# SparkFun_Thing_Plus_RP2350.net
KiCad netlist of a schematic drawn in EAGLE
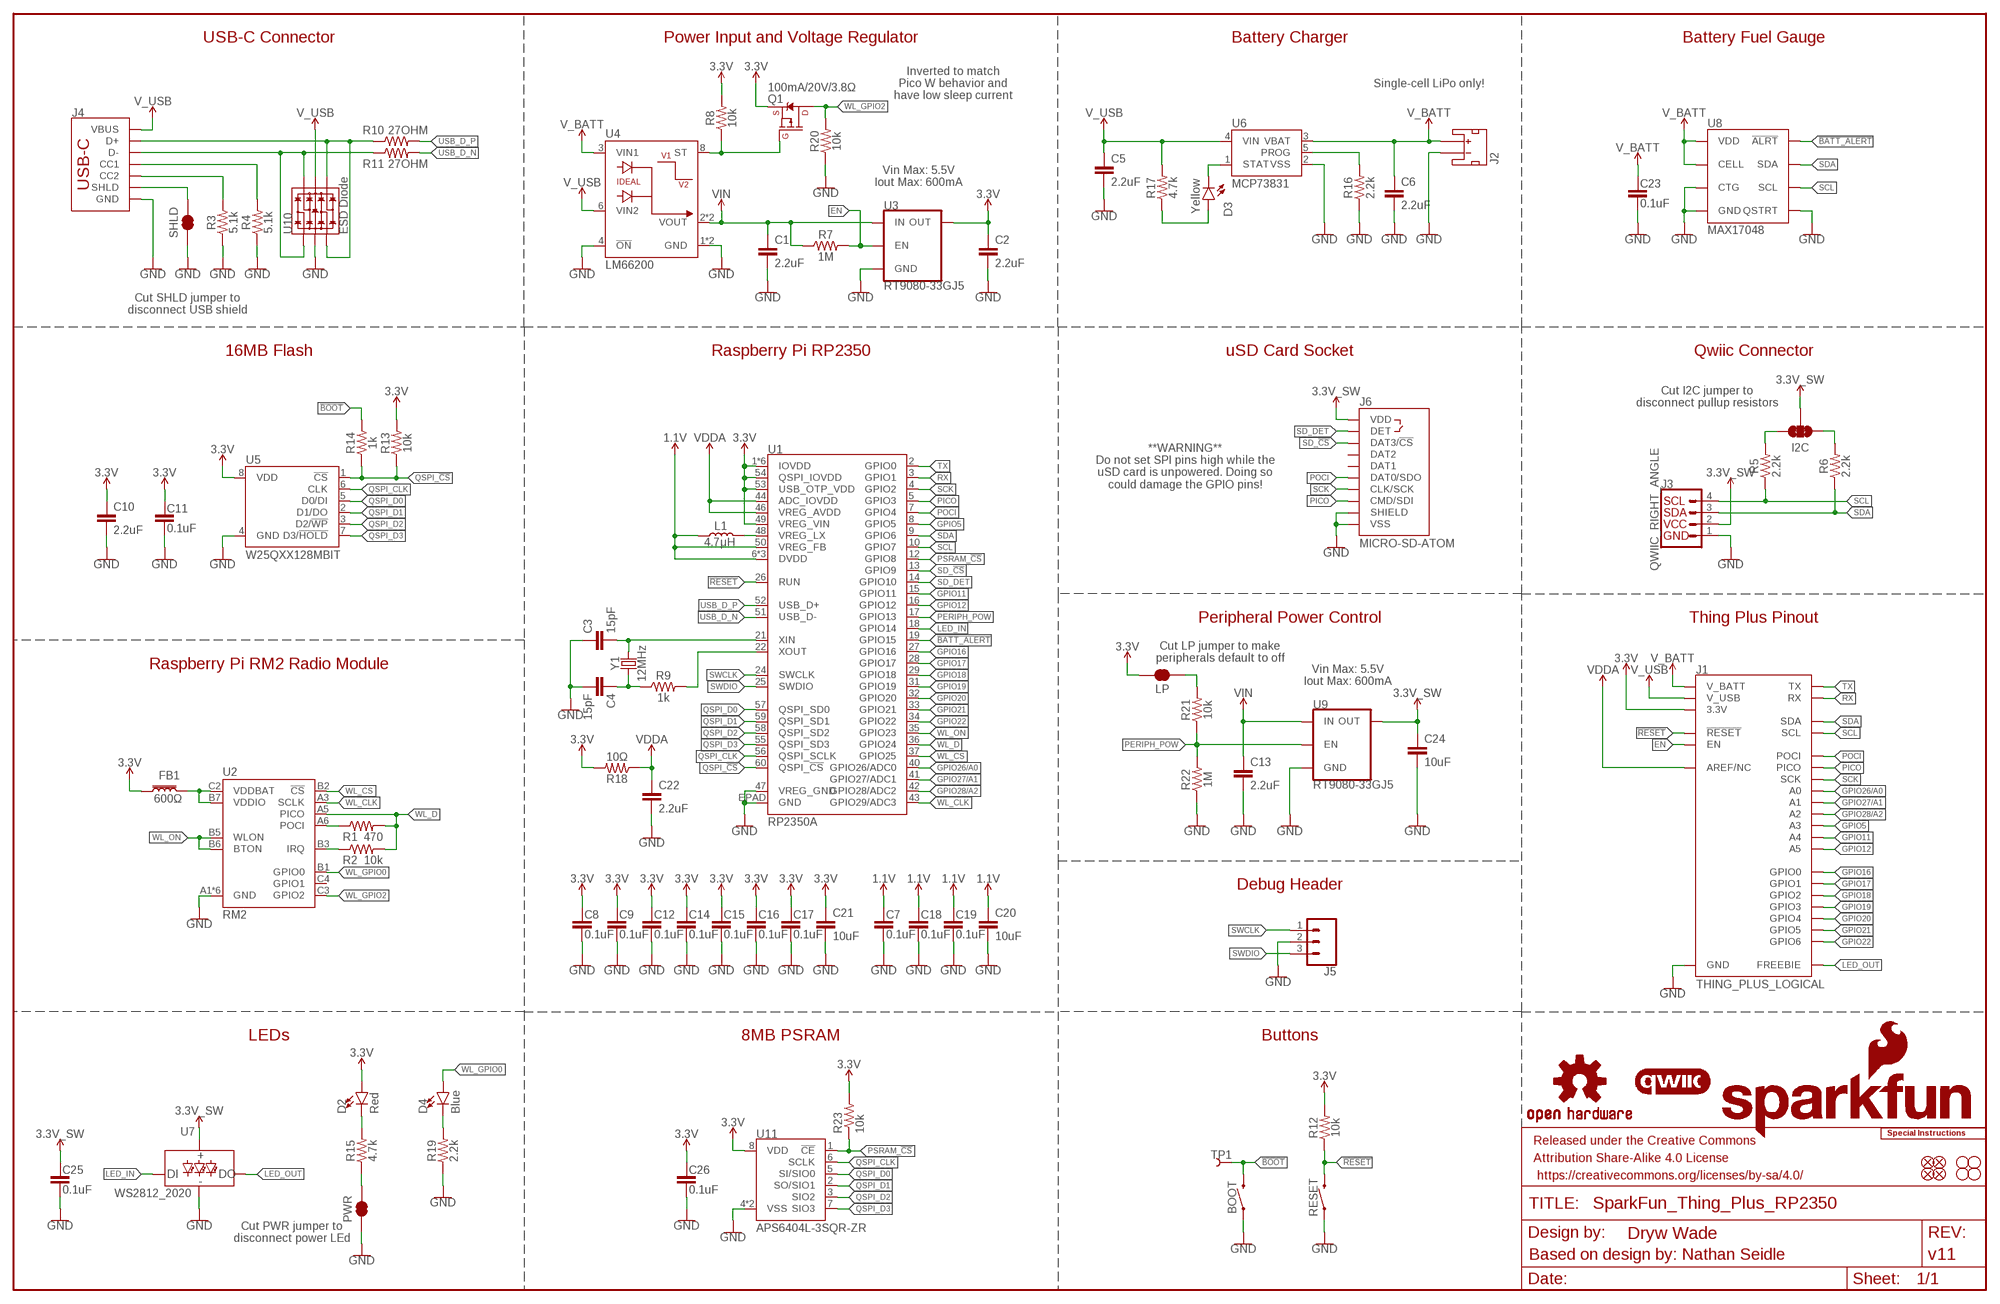
[diagram p0: schematic, sheet 1]

(export (version "E")
  (design (tool "Eeschema 10.0.6"))
  (components
    (comp (ref "BOOT")
      (value "MOMENTARY-SWITCH-SPST-SMD-4.6X2.8MM")
      (footprint "eagle-import:TACTILE_SWITCH_SMD_4.6X2.8MM")
      (libsource (lib "eagle-import") (part "MOMENTARY-SWITCH-SPST-SMD-4.6X2.8MM"))
    )
    (comp (ref "C1")
      (value "2.2uF")
      (footprint "eagle-import:0402-TIGHT")
      (libsource (lib "eagle-import") (part "2.2UF-0402_TIGHT-10V-10%-X5R"))
    )
    (comp (ref "C2")
      (value "2.2uF")
      (footprint "eagle-import:0402-TIGHT")
      (libsource (lib "eagle-import") (part "2.2UF-0402_TIGHT-10V-10%-X5R"))
    )
    (comp (ref "C3")
      (value "15pF")
      (footprint "eagle-import:0402-TIGHT")
      (libsource (lib "eagle-import") (part "15PF-0402T-50V-5%"))
    )
    (comp (ref "C4")
      (value "15pF")
      (footprint "eagle-import:0402-TIGHT")
      (libsource (lib "eagle-import") (part "15PF-0402T-50V-5%"))
    )
    (comp (ref "C5")
      (value "2.2uF")
      (footprint "eagle-import:0402-TIGHT")
      (libsource (lib "eagle-import") (part "2.2UF-0402_TIGHT-10V-10%-X5R"))
    )
    (comp (ref "C6")
      (value "2.2uF")
      (footprint "eagle-import:0402-TIGHT")
      (libsource (lib "eagle-import") (part "2.2UF-0402_TIGHT-10V-10%-X5R"))
    )
    (comp (ref "C7")
      (value "0.1uF")
      (footprint "eagle-import:0402-TIGHT")
      (libsource (lib "eagle-import") (part "0.1UF-0402T-6.3V-10%-X7R"))
    )
    (comp (ref "C8")
      (value "0.1uF")
      (footprint "eagle-import:0402-TIGHT")
      (libsource (lib "eagle-import") (part "0.1UF-0402T-6.3V-10%-X7R"))
    )
    (comp (ref "C9")
      (value "0.1uF")
      (footprint "eagle-import:0402-TIGHT")
      (libsource (lib "eagle-import") (part "0.1UF-0402T-6.3V-10%-X7R"))
    )
    (comp (ref "C10")
      (value "2.2uF")
      (footprint "eagle-import:0402-TIGHT")
      (libsource (lib "eagle-import") (part "2.2UF-0402_TIGHT-10V-10%-X5R"))
    )
    (comp (ref "C11")
      (value "0.1uF")
      (footprint "eagle-import:0402-TIGHT")
      (libsource (lib "eagle-import") (part "0.1UF-0402T-6.3V-10%-X7R"))
    )
    (comp (ref "C12")
      (value "0.1uF")
      (footprint "eagle-import:0402-TIGHT")
      (libsource (lib "eagle-import") (part "0.1UF-0402T-6.3V-10%-X7R"))
    )
    (comp (ref "C13")
      (value "2.2uF")
      (footprint "eagle-import:0402-TIGHT")
      (libsource (lib "eagle-import") (part "2.2UF-0402_TIGHT-10V-10%-X5R"))
    )
    (comp (ref "C14")
      (value "0.1uF")
      (footprint "eagle-import:0402-TIGHT")
      (libsource (lib "eagle-import") (part "0.1UF-0402T-6.3V-10%-X7R"))
    )
    (comp (ref "C15")
      (value "0.1uF")
      (footprint "eagle-import:0402-TIGHT")
      (libsource (lib "eagle-import") (part "0.1UF-0402T-6.3V-10%-X7R"))
    )
    (comp (ref "C16")
      (value "0.1uF")
      (footprint "eagle-import:0402-TIGHT")
      (libsource (lib "eagle-import") (part "0.1UF-0402T-6.3V-10%-X7R"))
    )
    (comp (ref "C17")
      (value "0.1uF")
      (footprint "eagle-import:0402-TIGHT")
      (libsource (lib "eagle-import") (part "0.1UF-0402T-6.3V-10%-X7R"))
    )
    (comp (ref "C18")
      (value "0.1uF")
      (footprint "eagle-import:0402-TIGHT")
      (libsource (lib "eagle-import") (part "0.1UF-0402T-6.3V-10%-X7R"))
    )
    (comp (ref "C19")
      (value "0.1uF")
      (footprint "eagle-import:0402-TIGHT")
      (libsource (lib "eagle-import") (part "0.1UF-0402T-6.3V-10%-X7R"))
    )
    (comp (ref "C20")
      (value "10uF")
      (footprint "eagle-import:0402-TIGHT")
      (libsource (lib "eagle-import") (part "10UF-0402T-6.3V-20%"))
    )
    (comp (ref "C21")
      (value "10uF")
      (footprint "eagle-import:0402-TIGHT")
      (libsource (lib "eagle-import") (part "10UF-0402T-6.3V-20%"))
    )
    (comp (ref "C22")
      (value "2.2uF")
      (footprint "eagle-import:0402-TIGHT")
      (libsource (lib "eagle-import") (part "2.2UF-0402_TIGHT-10V-10%-X5R"))
    )
    (comp (ref "C23")
      (value "0.1uF")
      (footprint "eagle-import:0402-TIGHT")
      (libsource (lib "eagle-import") (part "0.1UF-0402T-6.3V-10%-X7R"))
    )
    (comp (ref "C24")
      (value "10uF")
      (footprint "eagle-import:0402-TIGHT")
      (libsource (lib "eagle-import") (part "10UF-0402T-6.3V-20%"))
    )
    (comp (ref "C25")
      (value "0.1uF")
      (footprint "eagle-import:0402-TIGHT")
      (libsource (lib "eagle-import") (part "0.1UF-0402T-6.3V-10%-X7R"))
    )
    (comp (ref "C26")
      (value "0.1uF")
      (footprint "eagle-import:0402-TIGHT")
      (libsource (lib "eagle-import") (part "0.1UF-0402T-6.3V-10%-X7R"))
    )
    (comp (ref "D2")
      (value "Red")
      (footprint "eagle-import:LED-0603")
      (libsource (lib "eagle-import") (part "LED-RED_0603-KB"))
    )
    (comp (ref "D3")
      (value "Yellow")
      (footprint "eagle-import:LED-0603")
      (libsource (lib "eagle-import") (part "LED-YELLOW0603"))
    )
    (comp (ref "D4")
      (value "Blue")
      (footprint "eagle-import:LED-0603")
      (libsource (lib "eagle-import") (part "LED-BLUE0603"))
    )
    (comp (ref "FB1")
      (value "600Ω")
      (footprint "eagle-import:0805")
      (libsource (lib "eagle-import") (part "FERRITE_BEAD-0805-600Ω-100MHZ"))
    )
    (comp (ref "FD1")
      (value "FIDUCIALUFIDUCIAL")
      (footprint "eagle-import:FIDUCIAL-MICRO")
      (libsource (lib "eagle-import") (part "FIDUCIALUFIDUCIAL"))
    )
    (comp (ref "FD2")
      (value "FIDUCIALUFIDUCIAL")
      (footprint "eagle-import:FIDUCIAL-MICRO")
      (libsource (lib "eagle-import") (part "FIDUCIALUFIDUCIAL"))
    )
    (comp (ref "FD3")
      (value "FIDUCIALUFIDUCIAL")
      (footprint "eagle-import:FIDUCIAL-MICRO")
      (libsource (lib "eagle-import") (part "FIDUCIALUFIDUCIAL"))
    )
    (comp (ref "FD4")
      (value "FIDUCIALUFIDUCIAL")
      (footprint "eagle-import:FIDUCIAL-MICRO")
      (libsource (lib "eagle-import") (part "FIDUCIALUFIDUCIAL"))
    )
    (comp (ref "FRAME1")
      (value "FRAME-LEDGER")
      (footprint "eagle-import:CREATIVE_COMMONS")
      (fields (field (name "DESIGNER") "Dryw Wade") (field (name "REV") "v11"))
      (libsource (lib "eagle-import") (part "FRAME-LEDGER"))
    )
    (comp (ref "H1")
      (value "STAND-OFF")
      (footprint "eagle-import:STAND-OFF")
      (libsource (lib "eagle-import") (part "STAND-OFF"))
    )
    (comp (ref "H2")
      (value "STAND-OFF")
      (footprint "eagle-import:STAND-OFF")
      (libsource (lib "eagle-import") (part "STAND-OFF"))
    )
    (comp (ref "H3")
      (value "STAND-OFF")
      (footprint "eagle-import:STAND-OFF")
      (libsource (lib "eagle-import") (part "STAND-OFF"))
    )
    (comp (ref "H4")
      (value "STAND-OFF")
      (footprint "eagle-import:STAND-OFF")
      (libsource (lib "eagle-import") (part "STAND-OFF"))
    )
    (comp (ref "I2C")
      (value "JUMPER-SMT_3_2-NC_TRACE_SILK")
      (footprint "eagle-import:SMT-JUMPER_3_2-NC_TRACE_SILK")
      (libsource (lib "eagle-import") (part "JUMPER-SMT_3_2-NC_TRACE_SILK"))
    )
    (comp (ref "J1")
      (value "THING_PLUS_LOGICAL")
      (footprint "eagle-import:THING_PLUS")
      (libsource (lib "eagle-import") (part "THING_PLUS_LOGICAL"))
    )
    (comp (ref "J2")
      (value "JST_2MM_MALE")
      (footprint "eagle-import:JST-2-SMD")
      (libsource (lib "eagle-import") (part "JST_2MM_MALE"))
    )
    (comp (ref "J3")
      (value "QWIIC_RIGHT_ANGLE")
      (footprint "eagle-import:JST04_1MM_RA")
      (libsource (lib "eagle-import") (part "QWIIC_CONNECTORJS-1MM"))
    )
    (comp (ref "J4")
      (value "USB_C_4-LAYER_PADS")
      (footprint "eagle-import:USB-C-16P_4LAYER-PADS")
      (libsource (lib "eagle-import") (part "USB_C_4-LAYER_PADS"))
    )
    (comp (ref "J5")
      (value "CONN_031X03_NO_SILK")
      (footprint "eagle-import:1X03_NO_SILK")
      (libsource (lib "eagle-import") (part "CONN_031X03_NO_SILK"))
    )
    (comp (ref "J6")
      (value "MICRO-SD-ATOM")
      (footprint "eagle-import:MICROSD_ATOM")
      (libsource (lib "eagle-import") (part "MICRO-SD-ATOM"))
    )
    (comp (ref "L1")
      (value "4.7μH")
      (footprint "eagle-import:1008(2520)")
      (libsource (lib "eagle-import") (part "4.7μH_SHIELDED_INDUCTOR"))
    )
    (comp (ref "LOGO1")
      (value "SFE_LOGO_NAME_FLAME.1_INCH")
      (footprint "eagle-import:SFE_LOGO_NAME_FLAME_.1")
      (libsource (lib "eagle-import") (part "SFE_LOGO_NAME_FLAME.1_INCH"))
    )
    (comp (ref "LOGO2")
      (value "OSHW-LOGOS")
      (footprint "eagle-import:OSHW-LOGO-S")
      (libsource (lib "eagle-import") (part "OSHW-LOGOS"))
    )
    (comp (ref "LOGO3")
      (value "QWIIC_LOGO_4MM")
      (footprint "eagle-import:QWIIC_4MM")
      (libsource (lib "eagle-import") (part "QWIIC_LOGO_4MM"))
    )
    (comp (ref "LOGO5")
      (value "SPECIAL_INSTRUCTIONS-ORDERING")
      (footprint "eagle-import:ORDERING_INSTRUCTIONS")
      (libsource (lib "eagle-import") (part "SPECIAL_INSTRUCTIONS-ORDERING"))
    )
    (comp (ref "LP")
      (value "JUMPER-SMT_2_NC_TRACE_SILK")
      (footprint "eagle-import:SMT-JUMPER_2_NC_TRACE_SILK")
      (libsource (lib "eagle-import") (part "JUMPER-SMT_2_NC_TRACE_SILK"))
    )
    (comp (ref "PWR")
      (value "JUMPER-SMT_2_NC_TRACE_SILK")
      (footprint "eagle-import:SMT-JUMPER_2_NC_TRACE_SILK")
      (libsource (lib "eagle-import") (part "JUMPER-SMT_2_NC_TRACE_SILK"))
    )
    (comp (ref "Q1")
      (value "100mA/20V/3.8Ω")
      (footprint "eagle-import:SOT-416FL")
      (libsource (lib "eagle-import") (part "MOSFET_PCH-RE1C001ZPTL"))
    )
    (comp (ref "R1")
      (value "470")
      (footprint "eagle-import:0402-TIGHT")
      (libsource (lib "eagle-import") (part "470OHM-0402-TIGHT-1/16W-1%"))
    )
    (comp (ref "R2")
      (value "10k")
      (footprint "eagle-import:0402-TIGHT")
      (libsource (lib "eagle-import") (part "10KOHM-0402T-1/16W-1%"))
    )
    (comp (ref "R3")
      (value "5.1k")
      (footprint "eagle-import:0402-TIGHT")
      (libsource (lib "eagle-import") (part "5.1KOHM-0402T-1/16W-1%"))
    )
    (comp (ref "R4")
      (value "5.1k")
      (footprint "eagle-import:0402-TIGHT")
      (libsource (lib "eagle-import") (part "5.1KOHM-0402T-1/16W-1%"))
    )
    (comp (ref "R5")
      (value "2.2k")
      (footprint "eagle-import:0402-TIGHT")
      (libsource (lib "eagle-import") (part "2.2KOHM-0402T-1/16W-1%"))
    )
    (comp (ref "R6")
      (value "2.2k")
      (footprint "eagle-import:0402-TIGHT")
      (libsource (lib "eagle-import") (part "2.2KOHM-0402T-1/16W-1%"))
    )
    (comp (ref "R7")
      (value "1M")
      (footprint "eagle-import:0402-TIGHT")
      (libsource (lib "eagle-import") (part "1MOHM-0402T-1/16W-5%"))
    )
    (comp (ref "R8")
      (value "10k")
      (footprint "eagle-import:0402-TIGHT")
      (libsource (lib "eagle-import") (part "10KOHM-0402T-1/16W-1%"))
    )
    (comp (ref "R9")
      (value "1k")
      (footprint "eagle-import:0402-TIGHT")
      (libsource (lib "eagle-import") (part "1KOHM-0402T-1/16W-1%"))
    )
    (comp (ref "R10")
      (value "27OHM")
      (footprint "eagle-import:0402-TIGHT")
      (libsource (lib "eagle-import") (part "27OHM"))
    )
    (comp (ref "R11")
      (value "27OHM")
      (footprint "eagle-import:0402-TIGHT")
      (libsource (lib "eagle-import") (part "27OHM"))
    )
    (comp (ref "R12")
      (value "10k")
      (footprint "eagle-import:0402-TIGHT")
      (libsource (lib "eagle-import") (part "10KOHM-0402T-1/16W-1%"))
    )
    (comp (ref "R13")
      (value "10k")
      (footprint "eagle-import:0402-TIGHT")
      (libsource (lib "eagle-import") (part "10KOHM-0402T-1/16W-1%"))
    )
    (comp (ref "R14")
      (value "1k")
      (footprint "eagle-import:0402-TIGHT")
      (libsource (lib "eagle-import") (part "1KOHM-0402T-1/16W-1%"))
    )
    (comp (ref "R15")
      (value "4.7k")
      (footprint "eagle-import:0402-TIGHT")
      (libsource (lib "eagle-import") (part "4.7KOHM-0402T-1/16W-1%"))
    )
    (comp (ref "R16")
      (value "2.2k")
      (footprint "eagle-import:0402-TIGHT")
      (libsource (lib "eagle-import") (part "2.2KOHM-0402T-1/16W-1%"))
    )
    (comp (ref "R17")
      (value "4.7k")
      (footprint "eagle-import:0402-TIGHT")
      (libsource (lib "eagle-import") (part "4.7KOHM-0402T-1/16W-1%"))
    )
    (comp (ref "R18")
      (value "10Ω")
      (footprint "eagle-import:0402-TIGHT")
      (libsource (lib "eagle-import") (part "10OHM-0402-1/16W-5%"))
    )
    (comp (ref "R19")
      (value "2.2k")
      (footprint "eagle-import:0402-TIGHT")
      (libsource (lib "eagle-import") (part "2.2KOHM-0402T-1/16W-1%"))
    )
    (comp (ref "R20")
      (value "10k")
      (footprint "eagle-import:0402-TIGHT")
      (libsource (lib "eagle-import") (part "10KOHM-0402T-1/16W-1%"))
    )
    (comp (ref "R21")
      (value "10k")
      (footprint "eagle-import:0402-TIGHT")
      (libsource (lib "eagle-import") (part "10KOHM-0402T-1/16W-1%"))
    )
    (comp (ref "R22")
      (value "1M")
      (footprint "eagle-import:0402-TIGHT")
      (libsource (lib "eagle-import") (part "1MOHM-0402T-1/16W-5%"))
    )
    (comp (ref "R23")
      (value "10k")
      (footprint "eagle-import:0402-TIGHT")
      (libsource (lib "eagle-import") (part "10KOHM-0402T-1/16W-1%"))
    )
    (comp (ref "RESET")
      (value "MOMENTARY-SWITCH-SPST-SMD-4.6X2.8MM")
      (footprint "eagle-import:TACTILE_SWITCH_SMD_4.6X2.8MM")
      (libsource (lib "eagle-import") (part "MOMENTARY-SWITCH-SPST-SMD-4.6X2.8MM"))
    )
    (comp (ref "SHLD")
      (value "JUMPER-SMT_2_NC_TRACE_SILK")
      (footprint "eagle-import:SMT-JUMPER_2_NC_TRACE_SILK")
      (libsource (lib "eagle-import") (part "JUMPER-SMT_2_NC_TRACE_SILK"))
    )
    (comp (ref "TP1")
      (value "TEST-POINT3X5")
      (footprint "eagle-import:PAD.03X.05")
      (libsource (lib "eagle-import") (part "TEST-POINT3X5"))
    )
    (comp (ref "U1")
      (value "RP2350A")
      (footprint "eagle-import:RP2350A")
      (libsource (lib "eagle-import") (part "RP2350A"))
    )
    (comp (ref "U2")
      (value "RM2")
      (footprint "eagle-import:RM2")
      (libsource (lib "eagle-import") (part "RM2"))
    )
    (comp (ref "U3")
      (value "RT9080-33GJ5")
      (footprint "eagle-import:SOT23-5")
      (libsource (lib "eagle-import") (part "V_REG_RT9080-33GJ5"))
    )
    (comp (ref "U4")
      (value "LM66200")
      (footprint "eagle-import:SOT8")
      (libsource (lib "eagle-import") (part "IDEAL_DIODE_DUAL_LM66200"))
    )
    (comp (ref "U5")
      (value "W25QXX128MBIT")
      (footprint "eagle-import:WSON-8-6X5-SKINNY_CENTERPAD")
      (libsource (lib "eagle-import") (part "W25QXX128MBIT-6X5-SKINNY_CENTER"))
    )
    (comp (ref "U6")
      (value "MCP73831")
      (footprint "eagle-import:SOT23-5")
      (libsource (lib "eagle-import") (part "MCP73831"))
    )
    (comp (ref "U7")
      (value "WS2812_2020")
      (footprint "eagle-import:WS2812-2020")
      (libsource (lib "eagle-import") (part "WS2812_2020"))
    )
    (comp (ref "U8")
      (value "MAX17048")
      (footprint "eagle-import:DFN-8")
      (libsource (lib "eagle-import") (part "MAX17048DFN8"))
    )
    (comp (ref "U9")
      (value "RT9080-33GJ5")
      (footprint "eagle-import:SOT23-5")
      (libsource (lib "eagle-import") (part "V_REG_RT9080-33GJ5"))
    )
    (comp (ref "U10")
      (value "ESD Diode")
      (footprint "eagle-import:SOT-23-6")
      (libsource (lib "eagle-import") (part "TVS_DIODE_ARRAY_DT1042-04SO-7"))
    )
    (comp (ref "U11")
      (value "APS6404L-3SQR-ZR")
      (footprint "eagle-import:APS6404L-3SQR-ZR")
      (libsource (lib "eagle-import") (part "APS6404L-3SQR-ZR"))
    )
    (comp (ref "Y1")
      (value "12MHz")
      (footprint "eagle-import:CRYSTAL-SMD-2X2.5MM")
      (libsource (lib "eagle-import") (part "CRYSTAL-12MHZ"))
    )
  )
  (nets
    (net (code "1") (name "/PSRAM_~{CS}") (class "Default")
      (node (ref "R23") (pin "1") (pinfunction "1_1") (pintype "passive"))
      (node (ref "U1") (pin "12") (pinfunction "GPIO8_12") (pintype "bidirectional"))
      (node (ref "U11") (pin "1") (pinfunction "~{CE}_1") (pintype "bidirectional"))
    )
    (net (code "2") (name "/QSPI_~{CS}") (class "Default")
      (node (ref "R13") (pin "1") (pinfunction "1_1") (pintype "passive"))
      (node (ref "R14") (pin "1") (pinfunction "1_1") (pintype "passive"))
      (node (ref "U1") (pin "60") (pinfunction "QSPI_~{CS}_60") (pintype "bidirectional"))
      (node (ref "U5") (pin "1") (pinfunction "~{CS}_1") (pintype "bidirectional"))
    )
    (net (code "3") (name "/SD_~{CS}") (class "Default")
      (node (ref "J6") (pin "2") (pinfunction "DAT3/~{CS}_2") (pintype "bidirectional"))
      (node (ref "U1") (pin "13") (pinfunction "GPIO9_13") (pintype "bidirectional"))
    )
    (net (code "4") (name "/~{BATT_ALERT}") (class "Default")
      (node (ref "U1") (pin "19") (pinfunction "GPIO15_19") (pintype "bidirectional"))
      (node (ref "U8") (pin "5") (pinfunction "~{ALRT}_5") (pintype "bidirectional"))
    )
    (net (code "5") (name "/~{BOOT}") (class "Default")
      (node (ref "BOOT") (pin "3") (pinfunction "2_3") (pintype "passive"))
      (node (ref "BOOT") (pin "4") (pinfunction "2_4") (pintype "passive"))
      (node (ref "R14") (pin "2") (pinfunction "2_2") (pintype "passive"))
      (node (ref "TP1") (pin "1") (pinfunction "1_1") (pintype "bidirectional"))
    )
    (net (code "6") (name "/~{RESET}") (class "Default")
      (node (ref "J1") (pin "28") (pinfunction "~{RESET}_28") (pintype "bidirectional"))
      (node (ref "R12") (pin "1") (pinfunction "1_1") (pintype "passive"))
      (node (ref "RESET") (pin "3") (pinfunction "2_3") (pintype "passive"))
      (node (ref "RESET") (pin "4") (pinfunction "2_4") (pintype "passive"))
      (node (ref "U1") (pin "26") (pinfunction "RUN_26") (pintype "bidirectional"))
    )
    (net (code "7") (name "1.1V") (class "Default")
      (node (ref "C18") (pin "1") (pinfunction "1_1") (pintype "passive"))
      (node (ref "C19") (pin "1") (pinfunction "1_1") (pintype "passive"))
      (node (ref "C20") (pin "1") (pinfunction "1_1") (pintype "passive"))
      (node (ref "C7") (pin "1") (pinfunction "1_1") (pintype "passive"))
      (node (ref "L1") (pin "1") (pinfunction "1_1") (pintype "passive"))
      (node (ref "U1") (pin "23") (pinfunction "DVDD_23") (pintype "bidirectional"))
      (node (ref "U1") (pin "39") (pinfunction "DVDD_39") (pintype "bidirectional"))
      (node (ref "U1") (pin "50") (pinfunction "VREG_FB_50") (pintype "bidirectional"))
      (node (ref "U1") (pin "6") (pinfunction "DVDD_6") (pintype "bidirectional"))
    )
    (net (code "8") (name "3.3V") (class "Default")
      (node (ref "C10") (pin "1") (pinfunction "1_1") (pintype "passive"))
      (node (ref "C11") (pin "1") (pinfunction "1_1") (pintype "passive"))
      (node (ref "C12") (pin "1") (pinfunction "1_1") (pintype "passive"))
      (node (ref "C14") (pin "1") (pinfunction "1_1") (pintype "passive"))
      (node (ref "C15") (pin "1") (pinfunction "1_1") (pintype "passive"))
      (node (ref "C16") (pin "1") (pinfunction "1_1") (pintype "passive"))
      (node (ref "C17") (pin "1") (pinfunction "1_1") (pintype "passive"))
      (node (ref "C2") (pin "1") (pinfunction "1_1") (pintype "passive"))
      (node (ref "C21") (pin "1") (pinfunction "1_1") (pintype "passive"))
      (node (ref "C26") (pin "1") (pinfunction "1_1") (pintype "passive"))
      (node (ref "C8") (pin "1") (pinfunction "1_1") (pintype "passive"))
      (node (ref "C9") (pin "1") (pinfunction "1_1") (pintype "passive"))
      (node (ref "D2") (pin "A") (pinfunction "A_A") (pintype "passive"))
      (node (ref "FB1") (pin "1") (pinfunction "1_1") (pintype "passive"))
      (node (ref "J1") (pin "27") (pinfunction "3.3V_27") (pintype "bidirectional"))
      (node (ref "LP") (pin "2") (pinfunction "2_2") (pintype "passive"))
      (node (ref "Q1") (pin "2") (pinfunction "S_2") (pintype "bidirectional"))
      (node (ref "R12") (pin "2") (pinfunction "2_2") (pintype "passive"))
      (node (ref "R13") (pin "2") (pinfunction "2_2") (pintype "passive"))
      (node (ref "R18") (pin "2") (pinfunction "2_2") (pintype "passive"))
      (node (ref "R23") (pin "2") (pinfunction "2_2") (pintype "passive"))
      (node (ref "R8") (pin "2") (pinfunction "2_2") (pintype "passive"))
      (node (ref "U1") (pin "1") (pinfunction "IOVDD_1") (pintype "bidirectional"))
      (node (ref "U1") (pin "11") (pinfunction "IOVDD_11") (pintype "bidirectional"))
      (node (ref "U1") (pin "20") (pinfunction "IOVDD_20") (pintype "bidirectional"))
      (node (ref "U1") (pin "30") (pinfunction "IOVDD_30") (pintype "bidirectional"))
      (node (ref "U1") (pin "38") (pinfunction "IOVDD_38") (pintype "bidirectional"))
      (node (ref "U1") (pin "45") (pinfunction "IOVDD_45") (pintype "bidirectional"))
      (node (ref "U1") (pin "49") (pinfunction "VREG_VIN_49") (pintype "bidirectional"))
      (node (ref "U1") (pin "53") (pinfunction "USB_OTP_VDD_53") (pintype "bidirectional"))
      (node (ref "U1") (pin "54") (pinfunction "QSPI_IOVDD_54") (pintype "bidirectional"))
      (node (ref "U11") (pin "8") (pinfunction "VDD_8") (pintype "bidirectional"))
      (node (ref "U3") (pin "5") (pinfunction "OUT_5") (pintype "passive"))
      (node (ref "U5") (pin "8") (pinfunction "VDD_8") (pintype "bidirectional"))
    )
    (net (code "9") (name "3.3V_SW") (class "Default")
      (node (ref "C24") (pin "1") (pinfunction "1_1") (pintype "passive"))
      (node (ref "C25") (pin "1") (pinfunction "1_1") (pintype "passive"))
      (node (ref "I2C") (pin "2") (pinfunction "2_2") (pintype "passive"))
      (node (ref "J3") (pin "2") (pinfunction "2_2") (pintype "power_in"))
      (node (ref "J6") (pin "4") (pinfunction "VDD_4") (pintype "bidirectional"))
      (node (ref "U7") (pin "VCC") (pinfunction "VCC_VCC") (pintype "bidirectional"))
      (node (ref "U9") (pin "5") (pinfunction "OUT_5") (pintype "passive"))
    )
    (net (code "10") (name "EN") (class "Default")
      (node (ref "J1") (pin "11") (pinfunction "EN_11") (pintype "bidirectional"))
      (node (ref "R7") (pin "2") (pinfunction "2_2") (pintype "passive"))
      (node (ref "U3") (pin "3") (pinfunction "EN_3") (pintype "input"))
    )
    (net (code "11") (name "GND") (class "Default")
      (node (ref "BOOT") (pin "1") (pinfunction "1_1") (pintype "passive"))
      (node (ref "BOOT") (pin "2") (pinfunction "1_2") (pintype "passive"))
      (node (ref "C1") (pin "2") (pinfunction "2_2") (pintype "passive"))
      (node (ref "C10") (pin "2") (pinfunction "2_2") (pintype "passive"))
      (node (ref "C11") (pin "2") (pinfunction "2_2") (pintype "passive"))
      (node (ref "C12") (pin "2") (pinfunction "2_2") (pintype "passive"))
      (node (ref "C13") (pin "2") (pinfunction "2_2") (pintype "passive"))
      (node (ref "C14") (pin "2") (pinfunction "2_2") (pintype "passive"))
      (node (ref "C15") (pin "2") (pinfunction "2_2") (pintype "passive"))
      (node (ref "C16") (pin "2") (pinfunction "2_2") (pintype "passive"))
      (node (ref "C17") (pin "2") (pinfunction "2_2") (pintype "passive"))
      (node (ref "C18") (pin "2") (pinfunction "2_2") (pintype "passive"))
      (node (ref "C19") (pin "2") (pinfunction "2_2") (pintype "passive"))
      (node (ref "C2") (pin "2") (pinfunction "2_2") (pintype "passive"))
      (node (ref "C20") (pin "2") (pinfunction "2_2") (pintype "passive"))
      (node (ref "C21") (pin "2") (pinfunction "2_2") (pintype "passive"))
      (node (ref "C22") (pin "2") (pinfunction "2_2") (pintype "passive"))
      (node (ref "C23") (pin "2") (pinfunction "2_2") (pintype "passive"))
      (node (ref "C24") (pin "2") (pinfunction "2_2") (pintype "passive"))
      (node (ref "C25") (pin "2") (pinfunction "2_2") (pintype "passive"))
      (node (ref "C26") (pin "2") (pinfunction "2_2") (pintype "passive"))
      (node (ref "C3") (pin "1") (pinfunction "1_1") (pintype "passive"))
      (node (ref "C4") (pin "2") (pinfunction "2_2") (pintype "passive"))
      (node (ref "C5") (pin "2") (pinfunction "2_2") (pintype "passive"))
      (node (ref "C6") (pin "2") (pinfunction "2_2") (pintype "passive"))
      (node (ref "C7") (pin "2") (pinfunction "2_2") (pintype "passive"))
      (node (ref "C8") (pin "2") (pinfunction "2_2") (pintype "passive"))
      (node (ref "C9") (pin "2") (pinfunction "2_2") (pintype "passive"))
      (node (ref "J1") (pin "25") (pinfunction "GND_25") (pintype "bidirectional"))
      (node (ref "J2") (pin "1") (pinfunction "-_1") (pintype "bidirectional"))
      (node (ref "J3") (pin "1") (pinfunction "1_1") (pintype "power_in"))
      (node (ref "J4") (pin "GND") (pinfunction "GND_GND") (pintype "bidirectional"))
      (node (ref "J4") (pin "GND2") (pinfunction "GND_GND2") (pintype "bidirectional"))
      (node (ref "J5") (pin "2") (pinfunction "2_2") (pintype "passive"))
      (node (ref "J6") (pin "6") (pinfunction "VSS_6") (pintype "bidirectional"))
      (node (ref "J6") (pin "SHIELD1") (pinfunction "SHIELD_SHIELD1") (pintype "bidirectional"))
      (node (ref "J6") (pin "SHIELD2") (pinfunction "SHIELD_SHIELD2") (pintype "bidirectional"))
      (node (ref "J6") (pin "SHIELD3") (pinfunction "SHIELD_SHIELD3") (pintype "bidirectional"))
      (node (ref "J6") (pin "SHIELD4") (pinfunction "SHIELD_SHIELD4") (pintype "bidirectional"))
      (node (ref "PWR") (pin "1") (pinfunction "1_1") (pintype "passive"))
      (node (ref "R16") (pin "1") (pinfunction "1_1") (pintype "passive"))
      (node (ref "R19") (pin "1") (pinfunction "1_1") (pintype "passive"))
      (node (ref "R20") (pin "1") (pinfunction "1_1") (pintype "passive"))
      (node (ref "R22") (pin "1") (pinfunction "1_1") (pintype "passive"))
      (node (ref "R3") (pin "1") (pinfunction "1_1") (pintype "passive"))
      (node (ref "R4") (pin "1") (pinfunction "1_1") (pintype "passive"))
      (node (ref "RESET") (pin "1") (pinfunction "1_1") (pintype "passive"))
      (node (ref "RESET") (pin "2") (pinfunction "1_2") (pintype "passive"))
      (node (ref "SHLD") (pin "1") (pinfunction "1_1") (pintype "passive"))
      (node (ref "U1") (pin "47") (pinfunction "VREG_GND_47") (pintype "bidirectional"))
      (node (ref "U1") (pin "EPAD") (pinfunction "GND_EPAD") (pintype "bidirectional"))
      (node (ref "U10") (pin "2") (pinfunction "VSS_2") (pintype "bidirectional"))
      (node (ref "U11") (pin "4") (pinfunction "VSS_4") (pintype "bidirectional"))
      (node (ref "U11") (pin "9") (pinfunction "VSS_9") (pintype "bidirectional"))
      (node (ref "U2") (pin "A1") (pinfunction "GND_A1") (pintype "bidirectional"))
      (node (ref "U2") (pin "A4") (pinfunction "GND_A4") (pintype "bidirectional"))
      (node (ref "U2") (pin "A7") (pinfunction "GND_A7") (pintype "bidirectional"))
      (node (ref "U2") (pin "B4") (pinfunction "GND_B4") (pintype "bidirectional"))
      (node (ref "U2") (pin "C1") (pinfunction "GND_C1") (pintype "bidirectional"))
      (node (ref "U2") (pin "C7") (pinfunction "GND_C7") (pintype "bidirectional"))
      (node (ref "U3") (pin "2") (pinfunction "GND_2") (pintype "input"))
      (node (ref "U4") (pin "1") (pinfunction "GND_1") (pintype "bidirectional"))
      (node (ref "U4") (pin "4") (pinfunction "~{ON}_4") (pintype "bidirectional"))
      (node (ref "U4") (pin "5") (pinfunction "GND_5") (pintype "bidirectional"))
      (node (ref "U5") (pin "4") (pinfunction "GND_4") (pintype "bidirectional"))
      (node (ref "U6") (pin "2") (pinfunction "VSS_2") (pintype "power_in"))
      (node (ref "U7") (pin "GND") (pinfunction "GND_GND") (pintype "bidirectional"))
      (node (ref "U8") (pin "1") (pinfunction "CTG_1") (pintype "input"))
      (node (ref "U8") (pin "4") (pinfunction "GND_4") (pintype "bidirectional"))
      (node (ref "U8") (pin "6") (pinfunction "QSTRT_6") (pintype "bidirectional"))
      (node (ref "U8") (pin "9") (pinfunction "GND_9") (pintype "bidirectional"))
      (node (ref "U9") (pin "2") (pinfunction "GND_2") (pintype "input"))
    )
    (net (code "12") (name "GPIO5") (class "Default")
      (node (ref "J1") (pin "21") (pinfunction "A3_21") (pintype "bidirectional"))
      (node (ref "U1") (pin "8") (pinfunction "GPIO5_8") (pintype "bidirectional"))
    )
    (net (code "13") (name "GPIO11") (class "Default")
      (node (ref "J1") (pin "20") (pinfunction "A4_20") (pintype "bidirectional"))
      (node (ref "U1") (pin "15") (pinfunction "GPIO11_15") (pintype "bidirectional"))
    )
    (net (code "14") (name "GPIO12") (class "Default")
      (node (ref "J1") (pin "19") (pinfunction "A5_19") (pintype "bidirectional"))
      (node (ref "U1") (pin "16") (pinfunction "GPIO12_16") (pintype "bidirectional"))
    )
    (net (code "15") (name "GPIO16") (class "Default")
      (node (ref "J1") (pin "9") (pinfunction "GPIO0_9") (pintype "bidirectional"))
      (node (ref "U1") (pin "27") (pinfunction "GPIO16_27") (pintype "bidirectional"))
    )
    (net (code "16") (name "GPIO17") (class "Default")
      (node (ref "J1") (pin "8") (pinfunction "GPIO1_8") (pintype "bidirectional"))
      (node (ref "U1") (pin "28") (pinfunction "GPIO17_28") (pintype "bidirectional"))
    )
    (net (code "17") (name "GPIO18") (class "Default")
      (node (ref "J1") (pin "7") (pinfunction "GPIO2_7") (pintype "bidirectional"))
      (node (ref "U1") (pin "29") (pinfunction "GPIO18_29") (pintype "bidirectional"))
    )
    (net (code "18") (name "GPIO19") (class "Default")
      (node (ref "J1") (pin "6") (pinfunction "GPIO3_6") (pintype "bidirectional"))
      (node (ref "U1") (pin "31") (pinfunction "GPIO19_31") (pintype "bidirectional"))
    )
    (net (code "19") (name "GPIO20") (class "Default")
      (node (ref "J1") (pin "5") (pinfunction "GPIO4_5") (pintype "bidirectional"))
      (node (ref "U1") (pin "32") (pinfunction "GPIO20_32") (pintype "bidirectional"))
    )
    (net (code "20") (name "GPIO21") (class "Default")
      (node (ref "J1") (pin "4") (pinfunction "GPIO5_4") (pintype "bidirectional"))
      (node (ref "U1") (pin "33") (pinfunction "GPIO21_33") (pintype "bidirectional"))
    )
    (net (code "21") (name "GPIO22") (class "Default")
      (node (ref "J1") (pin "3") (pinfunction "GPIO6_3") (pintype "bidirectional"))
      (node (ref "U1") (pin "34") (pinfunction "GPIO22_34") (pintype "bidirectional"))
    )
    (net (code "22") (name "GPIO26{slash}A0") (class "Default")
      (node (ref "J1") (pin "24") (pinfunction "A0_24") (pintype "bidirectional"))
      (node (ref "U1") (pin "40") (pinfunction "GPIO26/ADC0_40") (pintype "bidirectional"))
    )
    (net (code "23") (name "GPIO27{slash}A1") (class "Default")
      (node (ref "J1") (pin "23") (pinfunction "A1_23") (pintype "bidirectional"))
      (node (ref "U1") (pin "41") (pinfunction "GPIO27/ADC1_41") (pintype "bidirectional"))
    )
    (net (code "24") (name "GPIO28{slash}A2") (class "Default")
      (node (ref "J1") (pin "22") (pinfunction "A2_22") (pintype "bidirectional"))
      (node (ref "U1") (pin "42") (pinfunction "GPIO28/ADC2_42") (pintype "bidirectional"))
    )
    (net (code "25") (name "LED_IN") (class "Default")
      (node (ref "U1") (pin "18") (pinfunction "GPIO14_18") (pintype "bidirectional"))
      (node (ref "U7") (pin "DI") (pinfunction "DI_DI") (pintype "bidirectional"))
    )
    (net (code "26") (name "LED_OUT") (class "Default")
      (node (ref "J1") (pin "13") (pinfunction "FREEBIE_13") (pintype "bidirectional"))
      (node (ref "U7") (pin "DO") (pinfunction "DO_DO") (pintype "bidirectional"))
    )
    (net (code "27") (name "Net-(D2-PadC)") (class "Default")
      (node (ref "D2") (pin "C") (pinfunction "C_C") (pintype "passive"))
      (node (ref "R15") (pin "2") (pinfunction "2_2") (pintype "passive"))
    )
    (net (code "28") (name "Net-(D3-PadA)") (class "Default")
      (node (ref "D3") (pin "A") (pinfunction "A_A") (pintype "passive"))
      (node (ref "R17") (pin "1") (pinfunction "1_1") (pintype "passive"))
    )
    (net (code "29") (name "Net-(D4-PadC)") (class "Default")
      (node (ref "D4") (pin "C") (pinfunction "C_C") (pintype "passive"))
      (node (ref "R19") (pin "2") (pinfunction "2_2") (pintype "passive"))
    )
    (net (code "30") (name "Net-(I2C-Pad1)") (class "Default")
      (node (ref "I2C") (pin "1") (pinfunction "1_1") (pintype "passive"))
      (node (ref "R6") (pin "2") (pinfunction "2_2") (pintype "passive"))
    )
    (net (code "31") (name "Net-(I2C-Pad3)") (class "Default")
      (node (ref "I2C") (pin "3") (pinfunction "3_3") (pintype "passive"))
      (node (ref "R5") (pin "2") (pinfunction "2_2") (pintype "passive"))
    )
    (net (code "32") (name "Net-(J4-CC1)") (class "Default")
      (node (ref "J4") (pin "A5") (pinfunction "CC1_A5") (pintype "bidirectional"))
      (node (ref "R4") (pin "2") (pinfunction "2_2") (pintype "passive"))
    )
    (net (code "33") (name "Net-(J4-CC2)") (class "Default")
      (node (ref "J4") (pin "B5") (pinfunction "CC2_B5") (pintype "bidirectional"))
      (node (ref "R3") (pin "2") (pinfunction "2_2") (pintype "passive"))
    )
    (net (code "34") (name "Net-(J4-SHLD-PadSHLD1)") (class "Default")
      (node (ref "J4") (pin "SHLD1") (pinfunction "SHLD_SHLD1") (pintype "bidirectional"))
      (node (ref "J4") (pin "SHLD2") (pinfunction "SHLD_SHLD2") (pintype "bidirectional"))
      (node (ref "J4") (pin "SHLD3") (pinfunction "SHLD_SHLD3") (pintype "bidirectional"))
      (node (ref "J4") (pin "SHLD4") (pinfunction "SHLD_SHLD4") (pintype "bidirectional"))
      (node (ref "SHLD") (pin "2") (pinfunction "2_2") (pintype "passive"))
    )
    (net (code "35") (name "Net-(LP-Pad1)") (class "Default")
      (node (ref "LP") (pin "1") (pinfunction "1_1") (pintype "passive"))
      (node (ref "R21") (pin "2") (pinfunction "2_2") (pintype "passive"))
    )
    (net (code "36") (name "Net-(PWR-Pad2)") (class "Default")
      (node (ref "PWR") (pin "2") (pinfunction "2_2") (pintype "passive"))
      (node (ref "R15") (pin "1") (pinfunction "1_1") (pintype "passive"))
    )
    (net (code "37") (name "Net-(Q1-G)") (class "Default")
      (node (ref "Q1") (pin "1") (pinfunction "G_1") (pintype "bidirectional"))
      (node (ref "R8") (pin "1") (pinfunction "1_1") (pintype "passive"))
      (node (ref "U4") (pin "8") (pinfunction "ST_8") (pintype "bidirectional"))
    )
    (net (code "38") (name "Net-(U1-VREG_LX)") (class "Default")
      (node (ref "L1") (pin "2") (pinfunction "2_2") (pintype "passive"))
      (node (ref "U1") (pin "48") (pinfunction "VREG_LX_48") (pintype "bidirectional"))
    )
    (net (code "39") (name "Net-(U1-XIN)") (class "Default")
      (node (ref "C3") (pin "2") (pinfunction "2_2") (pintype "passive"))
      (node (ref "U1") (pin "21") (pinfunction "XIN_21") (pintype "bidirectional"))
      (node (ref "Y1") (pin "P3") (pinfunction "2_P3") (pintype "passive"))
    )
    (net (code "40") (name "Net-(U1-XOUT)") (class "Default")
      (node (ref "R9") (pin "2") (pinfunction "2_2") (pintype "passive"))
      (node (ref "U1") (pin "22") (pinfunction "XOUT_22") (pintype "bidirectional"))
    )
    (net (code "41") (name "Net-(U2-IRQ)") (class "Default")
      (node (ref "R2") (pin "1") (pinfunction "1_1") (pintype "passive"))
      (node (ref "U2") (pin "B3") (pinfunction "IRQ_B3") (pintype "bidirectional"))
    )
    (net (code "42") (name "Net-(U2-POCI)") (class "Default")
      (node (ref "R1") (pin "1") (pinfunction "1_1") (pintype "passive"))
      (node (ref "U2") (pin "A6") (pinfunction "POCI_A6") (pintype "bidirectional"))
    )
    (net (code "43") (name "Net-(U2-VDDBAT)") (class "Default")
      (node (ref "FB1") (pin "2") (pinfunction "2_2") (pintype "passive"))
      (node (ref "U2") (pin "B7") (pinfunction "VDDIO_B7") (pintype "bidirectional"))
      (node (ref "U2") (pin "C2") (pinfunction "VDDBAT_C2") (pintype "bidirectional"))
    )
    (net (code "44") (name "Net-(U6-PROG)") (class "Default")
      (node (ref "R16") (pin "2") (pinfunction "2_2") (pintype "passive"))
      (node (ref "U6") (pin "5") (pinfunction "PROG_5") (pintype "input"))
    )
    (net (code "45") (name "Net-(U6-STAT)") (class "Default")
      (node (ref "D3") (pin "C") (pinfunction "C_C") (pintype "passive"))
      (node (ref "U6") (pin "1") (pinfunction "STAT_1") (pintype "output"))
    )
    (net (code "46") (name "Net-(U10-IO1)") (class "Default")
      (node (ref "J4") (pin "A7") (pinfunction "D-_A7") (pintype "bidirectional"))
      (node (ref "J4") (pin "B7") (pinfunction "D-_B7") (pintype "bidirectional"))
      (node (ref "R11") (pin "1") (pinfunction "1_1") (pintype "passive"))
      (node (ref "U10") (pin "1") (pinfunction "IO1_1") (pintype "bidirectional"))
      (node (ref "U10") (pin "6") (pinfunction "IO4_6") (pintype "bidirectional"))
    )
    (net (code "47") (name "Net-(U10-IO2)") (class "Default")
      (node (ref "J4") (pin "A6") (pinfunction "D+_A6") (pintype "bidirectional"))
      (node (ref "J4") (pin "B6") (pinfunction "D+_B6") (pintype "bidirectional"))
      (node (ref "R10") (pin "1") (pinfunction "1_1") (pintype "passive"))
      (node (ref "U10") (pin "3") (pinfunction "IO2_3") (pintype "bidirectional"))
      (node (ref "U10") (pin "4") (pinfunction "IO3_4") (pintype "bidirectional"))
    )
    (net (code "48") (name "Net-(Y1-1)") (class "Default")
      (node (ref "C4") (pin "1") (pinfunction "1_1") (pintype "passive"))
      (node (ref "R9") (pin "1") (pinfunction "1_1") (pintype "passive"))
      (node (ref "Y1") (pin "P1") (pinfunction "1_P1") (pintype "passive"))
    )
    (net (code "49") (name "PERIPH_POW") (class "Default")
      (node (ref "R21") (pin "1") (pinfunction "1_1") (pintype "passive"))
      (node (ref "R22") (pin "2") (pinfunction "2_2") (pintype "passive"))
      (node (ref "U1") (pin "17") (pinfunction "GPIO13_17") (pintype "bidirectional"))
      (node (ref "U9") (pin "3") (pinfunction "EN_3") (pintype "input"))
    )
    (net (code "50") (name "PICO") (class "Default")
      (node (ref "J1") (pin "17") (pinfunction "PICO_17") (pintype "bidirectional"))
      (node (ref "J6") (pin "3") (pinfunction "CMD/SDI_3") (pintype "bidirectional"))
      (node (ref "U1") (pin "5") (pinfunction "GPIO3_5") (pintype "bidirectional"))
    )
    (net (code "51") (name "POCI") (class "Default")
      (node (ref "J1") (pin "16") (pinfunction "POCI_16") (pintype "bidirectional"))
      (node (ref "J6") (pin "7") (pinfunction "DAT0/SDO_7") (pintype "bidirectional"))
      (node (ref "U1") (pin "7") (pinfunction "GPIO4_7") (pintype "bidirectional"))
    )
    (net (code "52") (name "QSPI_CLK") (class "Default")
      (node (ref "U1") (pin "56") (pinfunction "QSPI_SCLK_56") (pintype "bidirectional"))
      (node (ref "U11") (pin "6") (pinfunction "SCLK_6") (pintype "bidirectional"))
      (node (ref "U5") (pin "6") (pinfunction "CLK_6") (pintype "bidirectional"))
    )
    (net (code "53") (name "QSPI_D0") (class "Default")
      (node (ref "U1") (pin "57") (pinfunction "QSPI_SD0_57") (pintype "bidirectional"))
      (node (ref "U11") (pin "5") (pinfunction "SI/SIO0_5") (pintype "bidirectional"))
      (node (ref "U5") (pin "5") (pinfunction "D0/DI_5") (pintype "bidirectional"))
    )
    (net (code "54") (name "QSPI_D1") (class "Default")
      (node (ref "U1") (pin "59") (pinfunction "QSPI_SD1_59") (pintype "bidirectional"))
      (node (ref "U11") (pin "2") (pinfunction "SO/SIO1_2") (pintype "bidirectional"))
      (node (ref "U5") (pin "2") (pinfunction "D1/DO_2") (pintype "bidirectional"))
    )
    (net (code "55") (name "QSPI_D2") (class "Default")
      (node (ref "U1") (pin "58") (pinfunction "QSPI_SD2_58") (pintype "bidirectional"))
      (node (ref "U11") (pin "3") (pinfunction "SIO2_3") (pintype "bidirectional"))
      (node (ref "U5") (pin "3") (pinfunction "D2/~{WP}_3") (pintype "bidirectional"))
    )
    (net (code "56") (name "QSPI_D3") (class "Default")
      (node (ref "U1") (pin "55") (pinfunction "QSPI_SD3_55") (pintype "bidirectional"))
      (node (ref "U11") (pin "7") (pinfunction "SIO3_7") (pintype "bidirectional"))
      (node (ref "U5") (pin "7") (pinfunction "D3/~{HOLD}_7") (pintype "bidirectional"))
    )
    (net (code "57") (name "RX") (class "Default")
      (node (ref "J1") (pin "15") (pinfunction "RX_15") (pintype "bidirectional"))
      (node (ref "U1") (pin "3") (pinfunction "GPIO1_3") (pintype "bidirectional"))
    )
    (net (code "58") (name "SCK") (class "Default")
      (node (ref "J1") (pin "18") (pinfunction "SCK_18") (pintype "bidirectional"))
      (node (ref "J6") (pin "5") (pinfunction "CLK/SCK_5") (pintype "bidirectional"))
      (node (ref "U1") (pin "4") (pinfunction "GPIO2_4") (pintype "bidirectional"))
    )
    (net (code "59") (name "SCL") (class "Default")
      (node (ref "J1") (pin "2") (pinfunction "SCL_2") (pintype "bidirectional"))
      (node (ref "J3") (pin "4") (pinfunction "4_4") (pintype "passive"))
      (node (ref "R5") (pin "1") (pinfunction "1_1") (pintype "passive"))
      (node (ref "U1") (pin "10") (pinfunction "GPIO7_10") (pintype "bidirectional"))
      (node (ref "U8") (pin "7") (pinfunction "SCL_7") (pintype "output"))
    )
    (net (code "60") (name "SDA") (class "Default")
      (node (ref "J1") (pin "1") (pinfunction "SDA_1") (pintype "bidirectional"))
      (node (ref "J3") (pin "3") (pinfunction "3_3") (pintype "passive"))
      (node (ref "R6") (pin "1") (pinfunction "1_1") (pintype "passive"))
      (node (ref "U1") (pin "9") (pinfunction "GPIO6_9") (pintype "bidirectional"))
      (node (ref "U8") (pin "8") (pinfunction "SDA_8") (pintype "input"))
    )
    (net (code "61") (name "SD_DET") (class "Default")
      (node (ref "J6") (pin "9") (pinfunction "DET_9") (pintype "bidirectional"))
      (node (ref "U1") (pin "14") (pinfunction "GPIO10_14") (pintype "bidirectional"))
    )
    (net (code "62") (name "SWCLK") (class "Default")
      (node (ref "J5") (pin "1") (pinfunction "1_1") (pintype "passive"))
      (node (ref "U1") (pin "24") (pinfunction "SWCLK_24") (pintype "bidirectional"))
    )
    (net (code "63") (name "SWDIO") (class "Default")
      (node (ref "J5") (pin "3") (pinfunction "3_3") (pintype "passive"))
      (node (ref "U1") (pin "25") (pinfunction "SWDIO_25") (pintype "bidirectional"))
    )
    (net (code "64") (name "TX") (class "Default")
      (node (ref "J1") (pin "14") (pinfunction "TX_14") (pintype "bidirectional"))
      (node (ref "U1") (pin "2") (pinfunction "GPIO0_2") (pintype "bidirectional"))
    )
    (net (code "65") (name "USB_D_N") (class "Default")
      (node (ref "R11") (pin "2") (pinfunction "2_2") (pintype "passive"))
      (node (ref "U1") (pin "51") (pinfunction "USB_D-_51") (pintype "bidirectional"))
    )
    (net (code "66") (name "USB_D_P") (class "Default")
      (node (ref "R10") (pin "2") (pinfunction "2_2") (pintype "passive"))
      (node (ref "U1") (pin "52") (pinfunction "USB_D+_52") (pintype "bidirectional"))
    )
    (net (code "67") (name "VDDA") (class "Default")
      (node (ref "C22") (pin "1") (pinfunction "1_1") (pintype "passive"))
      (node (ref "J1") (pin "26") (pinfunction "AREF/NC_26") (pintype "bidirectional"))
      (node (ref "R18") (pin "1") (pinfunction "1_1") (pintype "passive"))
      (node (ref "U1") (pin "44") (pinfunction "ADC_IOVDD_44") (pintype "bidirectional"))
      (node (ref "U1") (pin "46") (pinfunction "VREG_AVDD_46") (pintype "bidirectional"))
    )
    (net (code "68") (name "VIN") (class "Default")
      (node (ref "C1") (pin "1") (pinfunction "1_1") (pintype "passive"))
      (node (ref "C13") (pin "1") (pinfunction "1_1") (pintype "passive"))
      (node (ref "R7") (pin "1") (pinfunction "1_1") (pintype "passive"))
      (node (ref "U3") (pin "1") (pinfunction "IN_1") (pintype "input"))
      (node (ref "U4") (pin "2") (pinfunction "VOUT_2") (pintype "bidirectional"))
      (node (ref "U4") (pin "7") (pinfunction "VOUT_7") (pintype "bidirectional"))
      (node (ref "U9") (pin "1") (pinfunction "IN_1") (pintype "input"))
    )
    (net (code "69") (name "V_BATT") (class "Default")
      (node (ref "C23") (pin "1") (pinfunction "1_1") (pintype "passive"))
      (node (ref "C6") (pin "1") (pinfunction "1_1") (pintype "passive"))
      (node (ref "J1") (pin "12") (pinfunction "V_BATT_12") (pintype "bidirectional"))
      (node (ref "J2") (pin "2") (pinfunction "+_2") (pintype "bidirectional"))
      (node (ref "U4") (pin "3") (pinfunction "VIN1_3") (pintype "bidirectional"))
      (node (ref "U6") (pin "3") (pinfunction "VBAT_3") (pintype "power_in"))
      (node (ref "U8") (pin "2") (pinfunction "CELL_2") (pintype "input"))
      (node (ref "U8") (pin "3") (pinfunction "VDD_3") (pintype "bidirectional"))
    )
    (net (code "70") (name "V_USB") (class "Default")
      (node (ref "C5") (pin "1") (pinfunction "1_1") (pintype "passive"))
      (node (ref "J1") (pin "10") (pinfunction "V_USB_10") (pintype "bidirectional"))
      (node (ref "J4") (pin "VBUS1") (pinfunction "VBUS_VBUS1") (pintype "bidirectional"))
      (node (ref "J4") (pin "VBUS2") (pinfunction "VBUS_VBUS2") (pintype "bidirectional"))
      (node (ref "R17") (pin "2") (pinfunction "2_2") (pintype "passive"))
      (node (ref "U10") (pin "5") (pinfunction "VCC_5") (pintype "bidirectional"))
      (node (ref "U4") (pin "6") (pinfunction "VIN2_6") (pintype "bidirectional"))
      (node (ref "U6") (pin "4") (pinfunction "VIN_4") (pintype "power_in"))
    )
    (net (code "71") (name "WL_CLK") (class "Default")
      (node (ref "U1") (pin "43") (pinfunction "GPIO29/ADC3_43") (pintype "bidirectional"))
      (node (ref "U2") (pin "A3") (pinfunction "SCLK_A3") (pintype "bidirectional"))
    )
    (net (code "72") (name "WL_CS") (class "Default")
      (node (ref "U1") (pin "37") (pinfunction "GPIO25_37") (pintype "bidirectional"))
      (node (ref "U2") (pin "B2") (pinfunction "~{CS}_B2") (pintype "bidirectional"))
    )
    (net (code "73") (name "WL_D") (class "Default")
      (node (ref "R1") (pin "2") (pinfunction "2_2") (pintype "passive"))
      (node (ref "R2") (pin "2") (pinfunction "2_2") (pintype "passive"))
      (node (ref "U1") (pin "36") (pinfunction "GPIO24_36") (pintype "bidirectional"))
      (node (ref "U2") (pin "A5") (pinfunction "PICO_A5") (pintype "bidirectional"))
    )
    (net (code "74") (name "WL_GPIO0") (class "Default")
      (node (ref "D4") (pin "A") (pinfunction "A_A") (pintype "passive"))
      (node (ref "U2") (pin "B1") (pinfunction "GPIO0_B1") (pintype "bidirectional"))
    )
    (net (code "75") (name "WL_GPIO2") (class "Default")
      (node (ref "Q1") (pin "3") (pinfunction "D_3") (pintype "bidirectional"))
      (node (ref "R20") (pin "2") (pinfunction "2_2") (pintype "passive"))
      (node (ref "U2") (pin "C3") (pinfunction "GPIO2_C3") (pintype "bidirectional"))
    )
    (net (code "76") (name "WL_ON") (class "Default")
      (node (ref "U1") (pin "35") (pinfunction "GPIO23_35") (pintype "bidirectional"))
      (node (ref "U2") (pin "B5") (pinfunction "WLON_B5") (pintype "bidirectional"))
      (node (ref "U2") (pin "B6") (pinfunction "BTON_B6") (pintype "bidirectional"))
    )
    (net (code "77") (name "unconnected-(J2-PAD1-PadNC1)") (class "Default")
      (node (ref "J2") (pin "NC1") (pinfunction "PAD1_NC1") (pintype "bidirectional"))
    )
    (net (code "78") (name "unconnected-(J2-PAD2-PadNC2)") (class "Default")
      (node (ref "J2") (pin "NC2") (pinfunction "PAD2_NC2") (pintype "bidirectional"))
    )
    (net (code "79") (name "unconnected-(J6-DAT1-Pad8)") (class "Default")
      (node (ref "J6") (pin "8") (pinfunction "DAT1_8") (pintype "bidirectional"))
    )
    (net (code "80") (name "unconnected-(J6-DAT2-Pad1)") (class "Default")
      (node (ref "J6") (pin "1") (pinfunction "DAT2_1") (pintype "bidirectional"))
    )
    (net (code "81") (name "unconnected-(U2-GPIO1-PadC4)") (class "Default")
      (node (ref "U2") (pin "C4") (pinfunction "GPIO1_C4") (pintype "bidirectional"))
    )
  )
)
